# ALLOCHIS_ADAPTER_v1_0.net
KiCad netlist of a schematic drawn in Altium Designer
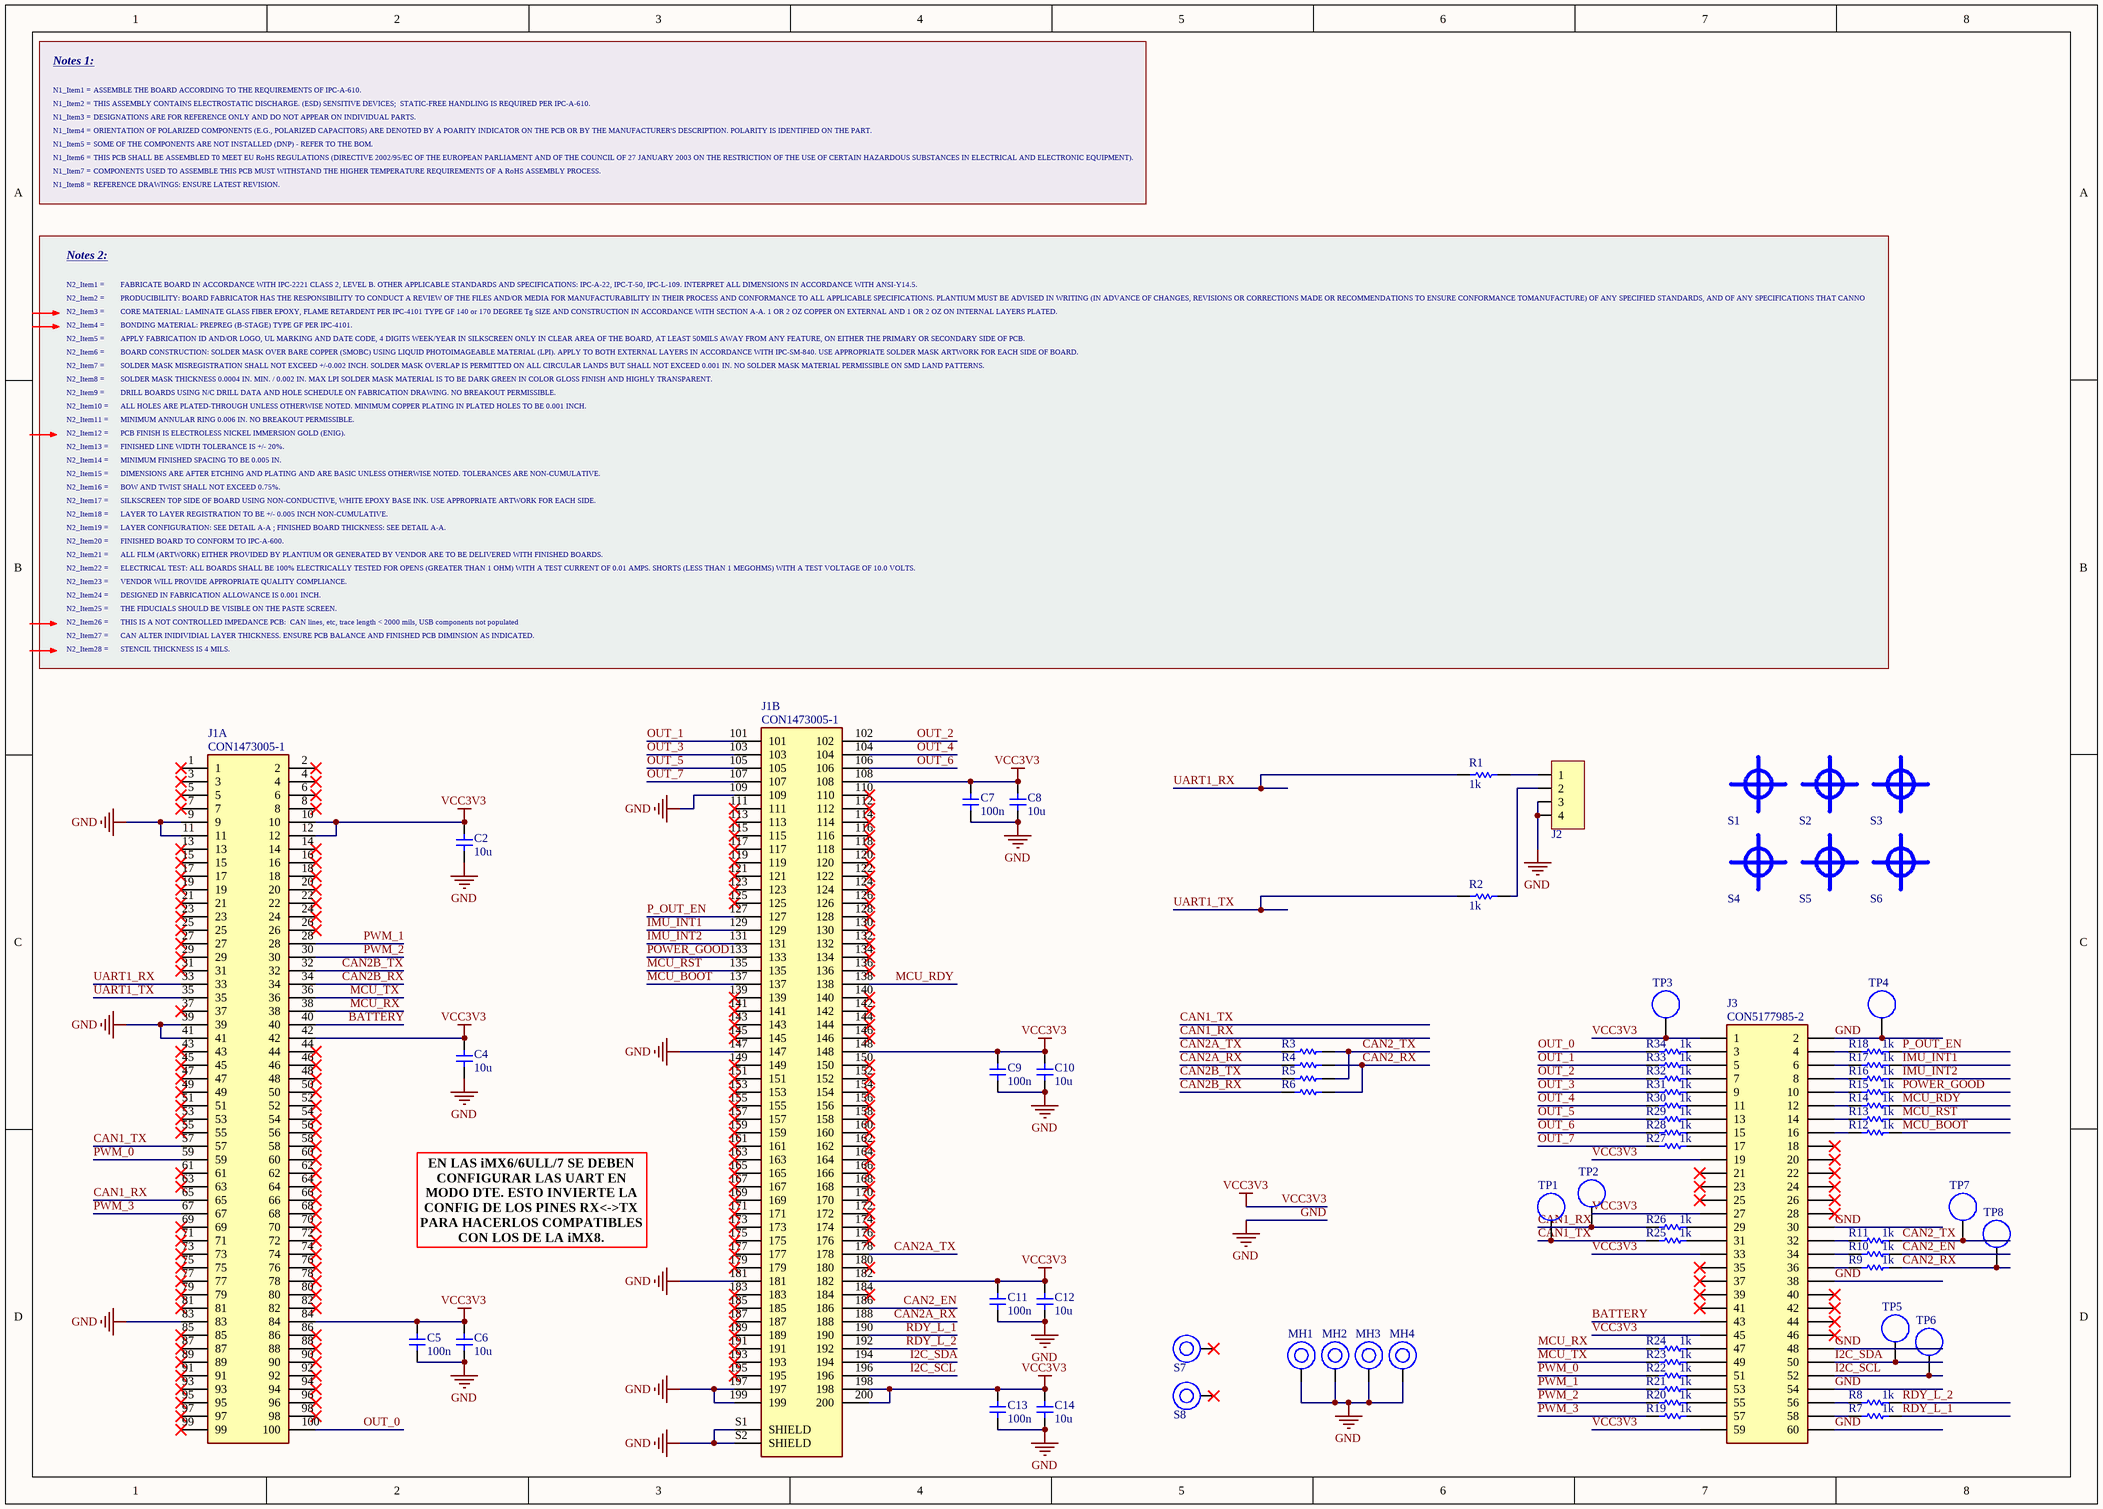
[diagram p0: ALLOCHIS_ADAPTER_v1.0.SchDoc]

(export (version "E")
  (design (tool "Eeschema 10.0.6"))
  (components
    (comp (ref "AssemblyNotes")
      (value "AssemblyNotes")
      (footprint "PlantiumFormat:ASSNOTES")
      (description "Assembly Notes")
      (fields
        (field (name "N1_ITEM8") "REFERENCE DRAWINGS: ENSURE LATEST REVISION.")
        (field (name "N1_ITEM7") "COMPONENTS USED TO ASSEMBLE THIS PCB MUST WITHSTAND THE HIGHER TEMPERATURE REQUIREMENTS OF A RoHS ASSEMBLY PROCESS.")
        (field (name "N1_ITEM6") "THIS PCB SHALL BE ASSEMBLED T0 MEET EU RoHS REGULATIONS (DIRECTIVE 2002/95/EC OF THE EUROPEAN PARLIAMENT AND OF THE COUNCIL OF 27 JANUARY 2003 ON THE RESTRICTION OF THE USE OF CERTAIN HAZARDOUS SUBSTANCES IN ELECTRICAL AND ELECTRONIC EQUIPMENT).")
        (field (name "N1_ITEM5") "SOME OF THE COMPONENTS ARE NOT INSTALLED (DNP) - REFER TO THE BOM.")
        (field (name "N1_ITEM4") "ORIENTATION OF POLARIZED COMPONENTS (E.G., POLARIZED CAPACITORS) ARE DENOTED BY A POARITY INDICATOR ON THE PCB OR BY THE MANUFACTURER'S DESCRIPTION. POLARITY IS IDENTIFIED ON THE PART.")
        (field (name "N1_ITEM3") "DESIGNATIONS ARE FOR REFERENCE ONLY AND DO NOT APPEAR ON INDIVIDUAL PARTS.")
        (field (name "N1_ITEM2") "THIS ASSEMBLY CONTAINS ELECTROSTATIC DISCHARGE. (ESD) SENSITIVE DEVICES;  STATIC-FREE HANDLING IS REQUIRED PER IPC-A-610.")
        (field (name "N1_ITEM1") "ASSEMBLE THE BOARD ACCORDING TO THE REQUIREMENTS OF IPC-A-610.")
      )
      (libsource (lib "PlantiumFormat") (part "AssemblyNotes"))
    )
    (comp (ref "C2")
      (value "10u")
      (footprint "C1206")
      (description "10 µF ±10% 50V Ceramic Capacitor X7R 1206 (3216 Metric)")
      (fields (field (name "MANUFACTURER PART NUMBER") "CL31B106KBHNNNE") (field (name "POWER") "NC"))
      (libsource (lib "PlantiumIntegratedLibrary") (part "CC106HKB1206W"))
    )
    (comp (ref "C4")
      (value "10u")
      (footprint "C1206")
      (description "10 µF ±10% 50V Ceramic Capacitor X7R 1206 (3216 Metric)")
      (fields (field (name "MANUFACTURER PART NUMBER") "CL31B106KBHNNNE") (field (name "POWER") "NC"))
      (libsource (lib "PlantiumIntegratedLibrary") (part "CC106HKB1206W"))
    )
    (comp (ref "C5")
      (value "100n")
      (footprint "C0603")
      (description "100 nF ±10% 50V Ceramic Capacitor X7R 0603 (1608 Metric)")
      (fields (field (name "MANUFACTURER PART NUMBER") "C0603C104K5RACTU") (field (name "POWER") "NC"))
      (libsource (lib "PlantiumIntegratedLibrary") (part "CC104HKB0603W"))
    )
    (comp (ref "C6")
      (value "10u")
      (footprint "C1206")
      (description "10 µF ±10% 50V Ceramic Capacitor X7R 1206 (3216 Metric)")
      (fields (field (name "MANUFACTURER PART NUMBER") "CL31B106KBHNNNE") (field (name "POWER") "NC"))
      (libsource (lib "PlantiumIntegratedLibrary") (part "CC106HKB1206W"))
    )
    (comp (ref "C7")
      (value "100n")
      (footprint "C0603")
      (description "100 nF ±10% 50V Ceramic Capacitor X7R 0603 (1608 Metric)")
      (fields (field (name "MANUFACTURER PART NUMBER") "C0603C104K5RACTU") (field (name "POWER") "NC"))
      (libsource (lib "PlantiumIntegratedLibrary") (part "CC104HKB0603W"))
    )
    (comp (ref "C8")
      (value "10u")
      (footprint "C1206")
      (description "10 µF ±10% 50V Ceramic Capacitor X7R 1206 (3216 Metric)")
      (fields (field (name "MANUFACTURER PART NUMBER") "CL31B106KBHNNNE") (field (name "POWER") "NC"))
      (libsource (lib "PlantiumIntegratedLibrary") (part "CC106HKB1206W"))
    )
    (comp (ref "C9")
      (value "100n")
      (footprint "C0603")
      (description "100 nF ±10% 50V Ceramic Capacitor X7R 0603 (1608 Metric)")
      (fields (field (name "MANUFACTURER PART NUMBER") "C0603C104K5RACTU") (field (name "POWER") "NC"))
      (libsource (lib "PlantiumIntegratedLibrary") (part "CC104HKB0603W"))
    )
    (comp (ref "C10")
      (value "10u")
      (footprint "C1206")
      (description "10 µF ±10% 50V Ceramic Capacitor X7R 1206 (3216 Metric)")
      (fields (field (name "MANUFACTURER PART NUMBER") "CL31B106KBHNNNE") (field (name "POWER") "NC"))
      (libsource (lib "PlantiumIntegratedLibrary") (part "CC106HKB1206W"))
    )
    (comp (ref "C11")
      (value "100n")
      (footprint "C0603")
      (description "100 nF ±10% 50V Ceramic Capacitor X7R 0603 (1608 Metric)")
      (fields (field (name "MANUFACTURER PART NUMBER") "C0603C104K5RACTU") (field (name "POWER") "NC"))
      (libsource (lib "PlantiumIntegratedLibrary") (part "CC104HKB0603W"))
    )
    (comp (ref "C12")
      (value "10u")
      (footprint "C1206")
      (description "10 µF ±10% 50V Ceramic Capacitor X7R 1206 (3216 Metric)")
      (fields (field (name "MANUFACTURER PART NUMBER") "CL31B106KBHNNNE") (field (name "POWER") "NC"))
      (libsource (lib "PlantiumIntegratedLibrary") (part "CC106HKB1206W"))
    )
    (comp (ref "C13")
      (value "100n")
      (footprint "C0603")
      (description "100 nF ±10% 50V Ceramic Capacitor X7R 0603 (1608 Metric)")
      (fields (field (name "MANUFACTURER PART NUMBER") "C0603C104K5RACTU") (field (name "POWER") "NC"))
      (libsource (lib "PlantiumIntegratedLibrary") (part "CC104HKB0603W"))
    )
    (comp (ref "C14")
      (value "10u")
      (footprint "C1206")
      (description "10 µF ±10% 50V Ceramic Capacitor X7R 1206 (3216 Metric)")
      (fields (field (name "MANUFACTURER PART NUMBER") "CL31B106KBHNNNE") (field (name "POWER") "NC"))
      (libsource (lib "PlantiumIntegratedLibrary") (part "CC106HKB1206W"))
    )
    (comp (ref "Fabrication Notes")
      (value "FabricationNotes")
      (footprint "PlantiumFormat:FABNOTES")
      (description "Fabrication Notes")
      (fields
        (field (name "N2_ITEM28") "STENCIL THICKNESS IS 4 MILS.")
        (field (name "N2_ITEM27") "CAN ALTER INIDIVIDIAL LAYER THICKNESS. ENSURE PCB BALANCE AND FINISHED PCB DIMINSION AS INDICATED.")
        (field (name "N2_ITEM26") "THIS IS A NOT CONTROLLED IMPEDANCE PCB:  CAN lines, etc, trace length < 2000 mils, USB components not populated")
        (field (name "N2_ITEM25") "THE FIDUCIALS SHOULD BE VISIBLE ON THE PASTE SCREEN.")
        (field (name "N2_ITEM24") "DESIGNED IN FABRICATION ALLOWANCE IS 0.001 INCH.")
        (field (name "N2_ITEM23") "VENDOR WILL PROVIDE APPROPRIATE QUALITY COMPLIANCE.")
        (field (name "N2_ITEM22") "ELECTRICAL TEST: ALL BOARDS SHALL BE 100% ELECTRICALLY TESTED FOR OPENS (GREATER THAN 1 OHM) WITH A TEST CURRENT OF 0.01 AMPS. SHORTS (LESS THAN 1 MEGOHMS) WITH A TEST VOLTAGE OF 10.0 VOLTS.")
        (field (name "N2_ITEM21") "ALL FILM (ARTWORK) EITHER PROVIDED BY PLANTIUM OR GENERATED BY VENDOR ARE TO BE DELIVERED WITH FINISHED BOARDS.")
        (field (name "N2_ITEM20") "FINISHED BOARD TO CONFORM TO IPC-A-600.")
        (field (name "N2_ITEM19") "LAYER CONFIGURATION: SEE DETAIL A-A ; FINISHED BOARD THICKNESS: SEE DETAIL A-A.")
        (field (name "N2_ITEM18") "LAYER TO LAYER REGISTRATION TO BE +/- 0.005 INCH NON-CUMULATIVE.")
        (field (name "N2_ITEM17") "SILKSCREEN TOP SIDE OF BOARD USING NON-CONDUCTIVE, WHITE EPOXY BASE INK. USE APPROPRIATE ARTWORK FOR EACH SIDE.")
        (field (name "N2_ITEM16") "BOW AND TWIST SHALL NOT EXCEED 0.75%.")
        (field (name "N2_ITEM15") "DIMENSIONS ARE AFTER ETCHING AND PLATING AND ARE BASIC UNLESS OTHERWISE NOTED. TOLERANCES ARE NON-CUMULATIVE.")
        (field (name "N2_ITEM14") "MINIMUM FINISHED SPACING TO BE 0.005 IN.")
        (field (name "N2_ITEM13") "FINISHED LINE WIDTH TOLERANCE IS +/- 20%.")
        (field (name "N2_ITEM12") "PCB FINISH IS ELECTROLESS NICKEL IMMERSION GOLD (ENIG).")
        (field (name "N2_ITEM11") "MINIMUM ANNULAR RING 0.006 IN. NO BREAKOUT PERMISSIBLE.")
        (field (name "N2_ITEM10") "ALL HOLES ARE PLATED-THROUGH UNLESS OTHERWISE NOTED. MINIMUM COPPER PLATING IN PLATED HOLES TO BE 0.001 INCH.")
        (field (name "N2_ITEM9") "DRILL BOARDS USING N/C DRILL DATA AND HOLE SCHEDULE ON FABRICATION DRAWING. NO BREAKOUT PERMISSIBLE.")
        (field (name "N2_ITEM8") "SOLDER MASK THICKNESS 0.0004 IN. MIN. / 0.002 IN. MAX LPI SOLDER MASK MATERIAL IS TO BE DARK GREEN IN COLOR GLOSS FINISH AND HIGHLY TRANSPARENT.")
        (field (name "N2_ITEM7") "SOLDER MASK MISREGISTRATION SHALL NOT EXCEED +/-0.002 INCH. SOLDER MASK OVERLAP IS PERMITTED ON ALL CIRCULAR LANDS BUT SHALL NOT EXCEED 0.001 IN. NO SOLDER MASK MATERIAL PERMISSIBLE ON SMD LAND PATTERNS.")
        (field (name "N2_ITEM6") "BOARD CONSTRUCTION: SOLDER MASK OVER BARE COPPER (SMOBC) USING LIQUID PHOTOIMAGEABLE MATERIAL (LPI). APPLY TO BOTH EXTERNAL LAYERS IN ACCORDANCE WITH IPC-SM-840. USE APPROPRIATE SOLDER MASK ARTWORK FOR EACH SIDE OF BOARD.")
        (field (name "N2_ITEM5") "APPLY FABRICATION ID AND/OR LOGO, UL MARKING AND DATE CODE, 4 DIGITS WEEK/YEAR IN SILKSCREEN ONLY IN CLEAR AREA OF THE BOARD, AT LEAST 50MILS AWAY FROM ANY FEATURE, ON EITHER THE PRIMARY OR SECONDARY SIDE OF PCB.")
        (field (name "N2_ITEM4") "BONDING MATERIAL: PREPREG (B-STAGE) TYPE GF PER IPC-4101.")
        (field (name "N2_ITEM3") "CORE MATERIAL: LAMINATE GLASS FIBER EPOXY, FLAME RETARDENT PER IPC-4101 TYPE GF 140 or 170 DEGREE Tg SIZE AND CONSTRUCTION IN ACCORDANCE WITH SECTION A-A. 1 OR 2 OZ COPPER ON EXTERNAL AND 1 OR 2 OZ ON INTERNAL LAYERS PLATED.")
        (field (name "N2_ITEM2") "PRODUCIBILITY: BOARD FABRICATOR HAS THE RESPONSIBILITY TO CONDUCT A REVIEW OF THE FILES AND/OR MEDIA FOR MANUFACTURABILITY IN THEIR PROCESS AND CONFORMANCE TO ALL APPLICABLE SPECIFICATIONS. PLANTIUM MUST BE ADVISED IN WRITING (IN ADVANCE OF CHANGES, REVISIONS OR CORRECTIONS MADE OR RECOMMENDATIONS TO ENSURE CONFORMANCE TOMANUFACTURE) OF ANY SPECIFIED STANDARDS, AND OF ANY SPECIFICATIONS THAT CANNOT BE MET.")
        (field (name "N2_ITEM1") "FABRICATE BOARD IN ACCORDANCE WITH IPC-2221 CLASS 2, LEVEL B. OTHER APPLICABLE STANDARDS AND SPECIFICATIONS: IPC-A-22, IPC-T-50, IPC-L-109. INTERPRET ALL DIMENSIONS IN ACCORDANCE WITH ANSI-Y14.5.")
      )
      (libsource (lib "PlantiumFormat") (part "FabricationNotes"))
    )
    (comp (ref "J1")
      (value "CON1473005-1")
      (footprint "TE_1473005-1 + SOM Toradex iMX")
      (description "200 Position Dual Row Right Angle Double Data Rate SO DIMM Memory Card Socket")
      (fields
        (field (name "MANUFACTURER PART NUMBER") "1473005-1")
        (field (name "MANUFACTURER") "TE Connectivity")
      )
      (libsource (lib "PlantiumIntegratedLibrary") (part "CON1473005-1"))
    )
    (comp (ref "J2")
      (value "CON-HEADER4")
      (footprint "HEADER4")
      (description "Header, 4-Pin")
      (libsource (lib "PlantiumIntegratedLibrary") (part "CON-HEADER4"))
    )
    (comp (ref "J3")
      (value "CON5177985-2")
      (footprint "TE_5177985-2")
      (description "60 Position Connector Receptacle, SMD, pitch 0.8mm")
      (fields
        (field (name "MANUFACTURER PART NUMBER") "5177985-2")
        (field (name "MANUFACTURER") "TE Connectivity AMP Connectors")
      )
      (libsource (lib "PlantiumIntegratedLibrary") (part "CON5177985-2"))
    )
    (comp (ref "MH1")
      (value "Mounting_Hole")
      (footprint "mounting_hole")
      (description "Mounting Hole")
      (fields (field (name "MANUFACTURER PART NUMBER") "NC"))
      (libsource (lib "PlantiumIntegratedLibrary") (part "Mounting_Hole"))
    )
    (comp (ref "MH2")
      (value "Mounting_Hole")
      (footprint "mounting_hole")
      (description "Mounting Hole")
      (fields (field (name "MANUFACTURER PART NUMBER") "NC"))
      (libsource (lib "PlantiumIntegratedLibrary") (part "Mounting_Hole"))
    )
    (comp (ref "MH3")
      (value "Mounting_Hole")
      (footprint "mounting_hole")
      (description "Mounting Hole")
      (fields (field (name "MANUFACTURER PART NUMBER") "NC"))
      (libsource (lib "PlantiumIntegratedLibrary") (part "Mounting_Hole"))
    )
    (comp (ref "MH4")
      (value "Mounting_Hole")
      (footprint "mounting_hole")
      (description "Mounting Hole")
      (fields (field (name "MANUFACTURER PART NUMBER") "NC"))
      (libsource (lib "PlantiumIntegratedLibrary") (part "Mounting_Hole"))
    )
    (comp (ref "R1")
      (value "1k")
      (footprint "R0603")
      (description "1 kOhms ±1% 0.1W, 1/10W Chip Resistor 0603 (1608 Metric) Automotive AEC-Q200 Thick Film")
      (fields (field (name "MANUFACTURER PART NUMBER") "ERJ-3EKF1001V") (field (name "POWER") "1/10W"))
      (libsource (lib "PlantiumIntegratedLibrary") (part "R1001RLF0603"))
    )
    (comp (ref "R2")
      (value "1k")
      (footprint "R0603")
      (description "1 kOhms ±1% 0.1W, 1/10W Chip Resistor 0603 (1608 Metric) Automotive AEC-Q200 Thick Film")
      (fields (field (name "MANUFACTURER PART NUMBER") "ERJ-3EKF1001V") (field (name "POWER") "1/10W"))
      (libsource (lib "PlantiumIntegratedLibrary") (part "R1001RLF0603"))
    )
    (comp (ref "R3")
      (value "R0000RLX0603")
      (footprint "R0603")
      (description "0 Ohms Jumper 0.1W, 1/10W Chip Resistor 0603 (1608 Metric) Automotive AEC-Q200 Thick Film")
      (fields (field (name "MANUFACTURER PART NUMBER") "ERJ-3GEY0R00V") (field (name "POWER") "1/10W"))
      (libsource (lib "PlantiumIntegratedLibrary") (part "R0000RLX0603"))
    )
    (comp (ref "R4")
      (value "R0000RLX0603")
      (footprint "R0603")
      (description "0 Ohms Jumper 0.1W, 1/10W Chip Resistor 0603 (1608 Metric) Automotive AEC-Q200 Thick Film")
      (fields (field (name "MANUFACTURER PART NUMBER") "ERJ-3GEY0R00V") (field (name "POWER") "1/10W"))
      (libsource (lib "PlantiumIntegratedLibrary") (part "R0000RLX0603"))
    )
    (comp (ref "R5")
      (value "R0000RLX0603")
      (footprint "R0603")
      (description "0 Ohms Jumper 0.1W, 1/10W Chip Resistor 0603 (1608 Metric) Automotive AEC-Q200 Thick Film")
      (fields (field (name "MANUFACTURER PART NUMBER") "ERJ-3GEY0R00V") (field (name "POWER") "1/10W"))
      (libsource (lib "PlantiumIntegratedLibrary") (part "R0000RLX0603"))
    )
    (comp (ref "R6")
      (value "R0000RLX0603")
      (footprint "R0603")
      (description "0 Ohms Jumper 0.1W, 1/10W Chip Resistor 0603 (1608 Metric) Automotive AEC-Q200 Thick Film")
      (fields (field (name "MANUFACTURER PART NUMBER") "ERJ-3GEY0R00V") (field (name "POWER") "1/10W"))
      (libsource (lib "PlantiumIntegratedLibrary") (part "R0000RLX0603"))
    )
    (comp (ref "R7")
      (value "1k")
      (footprint "R0603")
      (description "1 kOhms ±1% 0.1W, 1/10W Chip Resistor 0603 (1608 Metric) Automotive AEC-Q200 Thick Film")
      (fields (field (name "MANUFACTURER PART NUMBER") "ERJ-3EKF1001V") (field (name "POWER") "1/10W"))
      (libsource (lib "PlantiumIntegratedLibrary") (part "R1001RLF0603"))
    )
    (comp (ref "R8")
      (value "1k")
      (footprint "R0603")
      (description "1 kOhms ±1% 0.1W, 1/10W Chip Resistor 0603 (1608 Metric) Automotive AEC-Q200 Thick Film")
      (fields (field (name "MANUFACTURER PART NUMBER") "ERJ-3EKF1001V") (field (name "POWER") "1/10W"))
      (libsource (lib "PlantiumIntegratedLibrary") (part "R1001RLF0603"))
    )
    (comp (ref "R9")
      (value "1k")
      (footprint "R0603")
      (description "1 kOhms ±1% 0.1W, 1/10W Chip Resistor 0603 (1608 Metric) Automotive AEC-Q200 Thick Film")
      (fields (field (name "MANUFACTURER PART NUMBER") "ERJ-3EKF1001V") (field (name "POWER") "1/10W"))
      (libsource (lib "PlantiumIntegratedLibrary") (part "R1001RLF0603"))
    )
    (comp (ref "R10")
      (value "1k")
      (footprint "R0603")
      (description "1 kOhms ±1% 0.1W, 1/10W Chip Resistor 0603 (1608 Metric) Automotive AEC-Q200 Thick Film")
      (fields (field (name "MANUFACTURER PART NUMBER") "ERJ-3EKF1001V") (field (name "POWER") "1/10W"))
      (libsource (lib "PlantiumIntegratedLibrary") (part "R1001RLF0603"))
    )
    (comp (ref "R11")
      (value "1k")
      (footprint "R0603")
      (description "1 kOhms ±1% 0.1W, 1/10W Chip Resistor 0603 (1608 Metric) Automotive AEC-Q200 Thick Film")
      (fields (field (name "MANUFACTURER PART NUMBER") "ERJ-3EKF1001V") (field (name "POWER") "1/10W"))
      (libsource (lib "PlantiumIntegratedLibrary") (part "R1001RLF0603"))
    )
    (comp (ref "R12")
      (value "1k")
      (footprint "R0603")
      (description "1 kOhms ±1% 0.1W, 1/10W Chip Resistor 0603 (1608 Metric) Automotive AEC-Q200 Thick Film")
      (fields (field (name "MANUFACTURER PART NUMBER") "ERJ-3EKF1001V") (field (name "POWER") "1/10W"))
      (libsource (lib "PlantiumIntegratedLibrary") (part "R1001RLF0603"))
    )
    (comp (ref "R13")
      (value "1k")
      (footprint "R0603")
      (description "1 kOhms ±1% 0.1W, 1/10W Chip Resistor 0603 (1608 Metric) Automotive AEC-Q200 Thick Film")
      (fields (field (name "MANUFACTURER PART NUMBER") "ERJ-3EKF1001V") (field (name "POWER") "1/10W"))
      (libsource (lib "PlantiumIntegratedLibrary") (part "R1001RLF0603"))
    )
    (comp (ref "R14")
      (value "1k")
      (footprint "R0603")
      (description "1 kOhms ±1% 0.1W, 1/10W Chip Resistor 0603 (1608 Metric) Automotive AEC-Q200 Thick Film")
      (fields (field (name "MANUFACTURER PART NUMBER") "ERJ-3EKF1001V") (field (name "POWER") "1/10W"))
      (libsource (lib "PlantiumIntegratedLibrary") (part "R1001RLF0603"))
    )
    (comp (ref "R15")
      (value "1k")
      (footprint "R0603")
      (description "1 kOhms ±1% 0.1W, 1/10W Chip Resistor 0603 (1608 Metric) Automotive AEC-Q200 Thick Film")
      (fields (field (name "MANUFACTURER PART NUMBER") "ERJ-3EKF1001V") (field (name "POWER") "1/10W"))
      (libsource (lib "PlantiumIntegratedLibrary") (part "R1001RLF0603"))
    )
    (comp (ref "R16")
      (value "1k")
      (footprint "R0603")
      (description "1 kOhms ±1% 0.1W, 1/10W Chip Resistor 0603 (1608 Metric) Automotive AEC-Q200 Thick Film")
      (fields (field (name "MANUFACTURER PART NUMBER") "ERJ-3EKF1001V") (field (name "POWER") "1/10W"))
      (libsource (lib "PlantiumIntegratedLibrary") (part "R1001RLF0603"))
    )
    (comp (ref "R17")
      (value "1k")
      (footprint "R0603")
      (description "1 kOhms ±1% 0.1W, 1/10W Chip Resistor 0603 (1608 Metric) Automotive AEC-Q200 Thick Film")
      (fields (field (name "MANUFACTURER PART NUMBER") "ERJ-3EKF1001V") (field (name "POWER") "1/10W"))
      (libsource (lib "PlantiumIntegratedLibrary") (part "R1001RLF0603"))
    )
    (comp (ref "R18")
      (value "1k")
      (footprint "R0603")
      (description "1 kOhms ±1% 0.1W, 1/10W Chip Resistor 0603 (1608 Metric) Automotive AEC-Q200 Thick Film")
      (fields (field (name "MANUFACTURER PART NUMBER") "ERJ-3EKF1001V") (field (name "POWER") "1/10W"))
      (libsource (lib "PlantiumIntegratedLibrary") (part "R1001RLF0603"))
    )
    (comp (ref "R19")
      (value "1k")
      (footprint "R0603")
      (description "1 kOhms ±1% 0.1W, 1/10W Chip Resistor 0603 (1608 Metric) Automotive AEC-Q200 Thick Film")
      (fields (field (name "MANUFACTURER PART NUMBER") "ERJ-3EKF1001V") (field (name "POWER") "1/10W"))
      (libsource (lib "PlantiumIntegratedLibrary") (part "R1001RLF0603"))
    )
    (comp (ref "R20")
      (value "1k")
      (footprint "R0603")
      (description "1 kOhms ±1% 0.1W, 1/10W Chip Resistor 0603 (1608 Metric) Automotive AEC-Q200 Thick Film")
      (fields (field (name "MANUFACTURER PART NUMBER") "ERJ-3EKF1001V") (field (name "POWER") "1/10W"))
      (libsource (lib "PlantiumIntegratedLibrary") (part "R1001RLF0603"))
    )
    (comp (ref "R21")
      (value "1k")
      (footprint "R0603")
      (description "1 kOhms ±1% 0.1W, 1/10W Chip Resistor 0603 (1608 Metric) Automotive AEC-Q200 Thick Film")
      (fields (field (name "MANUFACTURER PART NUMBER") "ERJ-3EKF1001V") (field (name "POWER") "1/10W"))
      (libsource (lib "PlantiumIntegratedLibrary") (part "R1001RLF0603"))
    )
    (comp (ref "R22")
      (value "1k")
      (footprint "R0603")
      (description "1 kOhms ±1% 0.1W, 1/10W Chip Resistor 0603 (1608 Metric) Automotive AEC-Q200 Thick Film")
      (fields (field (name "MANUFACTURER PART NUMBER") "ERJ-3EKF1001V") (field (name "POWER") "1/10W"))
      (libsource (lib "PlantiumIntegratedLibrary") (part "R1001RLF0603"))
    )
    (comp (ref "R23")
      (value "1k")
      (footprint "R0603")
      (description "1 kOhms ±1% 0.1W, 1/10W Chip Resistor 0603 (1608 Metric) Automotive AEC-Q200 Thick Film")
      (fields (field (name "MANUFACTURER PART NUMBER") "ERJ-3EKF1001V") (field (name "POWER") "1/10W"))
      (libsource (lib "PlantiumIntegratedLibrary") (part "R1001RLF0603"))
    )
    (comp (ref "R24")
      (value "1k")
      (footprint "R0603")
      (description "1 kOhms ±1% 0.1W, 1/10W Chip Resistor 0603 (1608 Metric) Automotive AEC-Q200 Thick Film")
      (fields (field (name "MANUFACTURER PART NUMBER") "ERJ-3EKF1001V") (field (name "POWER") "1/10W"))
      (libsource (lib "PlantiumIntegratedLibrary") (part "R1001RLF0603"))
    )
    (comp (ref "R25")
      (value "1k")
      (footprint "R0603")
      (description "1 kOhms ±1% 0.1W, 1/10W Chip Resistor 0603 (1608 Metric) Automotive AEC-Q200 Thick Film")
      (fields (field (name "MANUFACTURER PART NUMBER") "ERJ-3EKF1001V") (field (name "POWER") "1/10W"))
      (libsource (lib "PlantiumIntegratedLibrary") (part "R1001RLF0603"))
    )
    (comp (ref "R26")
      (value "1k")
      (footprint "R0603")
      (description "1 kOhms ±1% 0.1W, 1/10W Chip Resistor 0603 (1608 Metric) Automotive AEC-Q200 Thick Film")
      (fields (field (name "MANUFACTURER PART NUMBER") "ERJ-3EKF1001V") (field (name "POWER") "1/10W"))
      (libsource (lib "PlantiumIntegratedLibrary") (part "R1001RLF0603"))
    )
    (comp (ref "R27")
      (value "1k")
      (footprint "R0603")
      (description "1 kOhms ±1% 0.1W, 1/10W Chip Resistor 0603 (1608 Metric) Automotive AEC-Q200 Thick Film")
      (fields (field (name "MANUFACTURER PART NUMBER") "ERJ-3EKF1001V") (field (name "POWER") "1/10W"))
      (libsource (lib "PlantiumIntegratedLibrary") (part "R1001RLF0603"))
    )
    (comp (ref "R28")
      (value "1k")
      (footprint "R0603")
      (description "1 kOhms ±1% 0.1W, 1/10W Chip Resistor 0603 (1608 Metric) Automotive AEC-Q200 Thick Film")
      (fields (field (name "MANUFACTURER PART NUMBER") "ERJ-3EKF1001V") (field (name "POWER") "1/10W"))
      (libsource (lib "PlantiumIntegratedLibrary") (part "R1001RLF0603"))
    )
    (comp (ref "R29")
      (value "1k")
      (footprint "R0603")
      (description "1 kOhms ±1% 0.1W, 1/10W Chip Resistor 0603 (1608 Metric) Automotive AEC-Q200 Thick Film")
      (fields (field (name "MANUFACTURER PART NUMBER") "ERJ-3EKF1001V") (field (name "POWER") "1/10W"))
      (libsource (lib "PlantiumIntegratedLibrary") (part "R1001RLF0603"))
    )
    (comp (ref "R30")
      (value "1k")
      (footprint "R0603")
      (description "1 kOhms ±1% 0.1W, 1/10W Chip Resistor 0603 (1608 Metric) Automotive AEC-Q200 Thick Film")
      (fields (field (name "MANUFACTURER PART NUMBER") "ERJ-3EKF1001V") (field (name "POWER") "1/10W"))
      (libsource (lib "PlantiumIntegratedLibrary") (part "R1001RLF0603"))
    )
    (comp (ref "R31")
      (value "1k")
      (footprint "R0603")
      (description "1 kOhms ±1% 0.1W, 1/10W Chip Resistor 0603 (1608 Metric) Automotive AEC-Q200 Thick Film")
      (fields (field (name "MANUFACTURER PART NUMBER") "ERJ-3EKF1001V") (field (name "POWER") "1/10W"))
      (libsource (lib "PlantiumIntegratedLibrary") (part "R1001RLF0603"))
    )
    (comp (ref "R32")
      (value "1k")
      (footprint "R0603")
      (description "1 kOhms ±1% 0.1W, 1/10W Chip Resistor 0603 (1608 Metric) Automotive AEC-Q200 Thick Film")
      (fields (field (name "MANUFACTURER PART NUMBER") "ERJ-3EKF1001V") (field (name "POWER") "1/10W"))
      (libsource (lib "PlantiumIntegratedLibrary") (part "R1001RLF0603"))
    )
    (comp (ref "R33")
      (value "1k")
      (footprint "R0603")
      (description "1 kOhms ±1% 0.1W, 1/10W Chip Resistor 0603 (1608 Metric) Automotive AEC-Q200 Thick Film")
      (fields (field (name "MANUFACTURER PART NUMBER") "ERJ-3EKF1001V") (field (name "POWER") "1/10W"))
      (libsource (lib "PlantiumIntegratedLibrary") (part "R1001RLF0603"))
    )
    (comp (ref "R34")
      (value "1k")
      (footprint "R0603")
      (description "1 kOhms ±1% 0.1W, 1/10W Chip Resistor 0603 (1608 Metric) Automotive AEC-Q200 Thick Film")
      (fields (field (name "MANUFACTURER PART NUMBER") "ERJ-3EKF1001V") (field (name "POWER") "1/10W"))
      (libsource (lib "PlantiumIntegratedLibrary") (part "R1001RLF0603"))
    )
    (comp (ref "S1")
      (value "Fiducial")
      (footprint "FIDROUND1X2")
      (description "Fiducial Mark")
      (fields (field (name "TOLERANCE") "NC"))
      (libsource (lib "PlantiumIntegratedLibrary") (part "Fiducial"))
    )
    (comp (ref "S2")
      (value "Fiducial")
      (footprint "FIDROUND1X2")
      (description "Fiducial Mark")
      (fields (field (name "TOLERANCE") "NC"))
      (libsource (lib "PlantiumIntegratedLibrary") (part "Fiducial"))
    )
    (comp (ref "S3")
      (value "Fiducial")
      (footprint "FIDROUND1X2")
      (description "Fiducial Mark")
      (fields (field (name "TOLERANCE") "NC"))
      (libsource (lib "PlantiumIntegratedLibrary") (part "Fiducial"))
    )
    (comp (ref "S4")
      (value "Fiducial")
      (footprint "FIDROUND1X2")
      (description "Fiducial Mark")
      (fields (field (name "TOLERANCE") "NC"))
      (libsource (lib "PlantiumIntegratedLibrary") (part "Fiducial"))
    )
    (comp (ref "S5")
      (value "Fiducial")
      (footprint "FIDROUND1X2")
      (description "Fiducial Mark")
      (fields (field (name "TOLERANCE") "NC"))
      (libsource (lib "PlantiumIntegratedLibrary") (part "Fiducial"))
    )
    (comp (ref "S6")
      (value "Fiducial")
      (footprint "FIDROUND1X2")
      (description "Fiducial Mark")
      (fields (field (name "TOLERANCE") "NC"))
      (libsource (lib "PlantiumIntegratedLibrary") (part "Fiducial"))
    )
    (comp (ref "S7")
      (value "ACC74030243R")
      (footprint "9774030243")
      (description "Steel Spacer. Round Standoff Threaded M2x0.4 Steel 0.118\" (3.00mm)")
      (fields
        (field (name "MANUFACTURER PART NUMBER") "9774030243R")
        (field (name "MANUFACTURER") "Würth Elektronik")
      )
      (libsource (lib "PlantiumIntegratedLibrary") (part "ACC74030243R"))
    )
    (comp (ref "S8")
      (value "ACC74030243R")
      (footprint "9774030243")
      (description "Steel Spacer. Round Standoff Threaded M2x0.4 Steel 0.118\" (3.00mm)")
      (fields
        (field (name "MANUFACTURER PART NUMBER") "9774030243R")
        (field (name "MANUFACTURER") "Würth Elektronik")
      )
      (libsource (lib "PlantiumIntegratedLibrary") (part "ACC74030243R"))
    )
    (comp (ref "TP1")
      (value "Test_Point")
      (footprint "Test_point")
      (description "Test point")
      (fields (field (name "MANUFACTURER PART NUMBER") "NC"))
      (libsource (lib "PlantiumIntegratedLibrary") (part "Test_Point"))
    )
    (comp (ref "TP2")
      (value "Test_Point")
      (footprint "Test_point")
      (description "Test point")
      (fields (field (name "MANUFACTURER PART NUMBER") "NC"))
      (libsource (lib "PlantiumIntegratedLibrary") (part "Test_Point"))
    )
    (comp (ref "TP3")
      (value "Test_Point")
      (footprint "Test_point")
      (description "Test point")
      (fields (field (name "MANUFACTURER PART NUMBER") "NC"))
      (libsource (lib "PlantiumIntegratedLibrary") (part "Test_Point"))
    )
    (comp (ref "TP4")
      (value "Test_Point")
      (footprint "Test_point")
      (description "Test point")
      (fields (field (name "MANUFACTURER PART NUMBER") "NC"))
      (libsource (lib "PlantiumIntegratedLibrary") (part "Test_Point"))
    )
    (comp (ref "TP5")
      (value "Test_Point")
      (footprint "Test_point")
      (description "Test point")
      (fields (field (name "MANUFACTURER PART NUMBER") "NC"))
      (libsource (lib "PlantiumIntegratedLibrary") (part "Test_Point"))
    )
    (comp (ref "TP6")
      (value "Test_Point")
      (footprint "Test_point")
      (description "Test point")
      (fields (field (name "MANUFACTURER PART NUMBER") "NC"))
      (libsource (lib "PlantiumIntegratedLibrary") (part "Test_Point"))
    )
    (comp (ref "TP7")
      (value "Test_Point")
      (footprint "Test_point")
      (description "Test point")
      (fields (field (name "MANUFACTURER PART NUMBER") "NC"))
      (libsource (lib "PlantiumIntegratedLibrary") (part "Test_Point"))
    )
    (comp (ref "TP8")
      (value "Test_Point")
      (footprint "Test_point")
      (description "Test point")
      (fields (field (name "MANUFACTURER PART NUMBER") "NC"))
      (libsource (lib "PlantiumIntegratedLibrary") (part "Test_Point"))
    )
  )
  (nets
    (net (code "1") (name "/BATTERY") (class "Default")
      (node (ref "J1") (pin "40") (pinfunction "40_40") (pintype "passive"))
      (node (ref "J3") (pin "43") (pinfunction "43_43") (pintype "passive"))
    )
    (net (code "2") (name "/CAN1_RX") (class "Default")
      (node (ref "J1") (pin "65") (pinfunction "65_65") (pintype "passive"))
      (node (ref "R26") (pin "1") (pinfunction "1_1") (pintype "passive"))
      (node (ref "TP2") (pin "1") (pinfunction "1_1") (pintype "passive"))
    )
    (net (code "3") (name "/CAN1_TX") (class "Default")
      (node (ref "J1") (pin "57") (pinfunction "57_57") (pintype "passive"))
      (node (ref "R25") (pin "1") (pinfunction "1_1") (pintype "passive"))
      (node (ref "TP1") (pin "1") (pinfunction "1_1") (pintype "passive"))
    )
    (net (code "4") (name "/CAN2A_RX") (class "Default")
      (node (ref "J1") (pin "188") (pinfunction "188_188") (pintype "passive"))
      (node (ref "R4") (pin "1") (pinfunction "1_1") (pintype "passive"))
    )
    (net (code "5") (name "/CAN2A_TX") (class "Default")
      (node (ref "J1") (pin "178") (pinfunction "178_178") (pintype "passive"))
      (node (ref "R3") (pin "1") (pinfunction "1_1") (pintype "passive"))
    )
    (net (code "6") (name "/CAN2B_RX") (class "Default")
      (node (ref "J1") (pin "34") (pinfunction "34_34") (pintype "passive"))
      (node (ref "R6") (pin "1") (pinfunction "1_1") (pintype "passive"))
    )
    (net (code "7") (name "/CAN2B_TX") (class "Default")
      (node (ref "J1") (pin "32") (pinfunction "32_32") (pintype "passive"))
      (node (ref "R5") (pin "1") (pinfunction "1_1") (pintype "passive"))
    )
    (net (code "8") (name "/CAN2_EN") (class "Default")
      (node (ref "J1") (pin "186") (pinfunction "186_186") (pintype "passive"))
      (node (ref "R10") (pin "2") (pinfunction "2_2") (pintype "passive"))
    )
    (net (code "9") (name "/CAN2_RX") (class "Default")
      (node (ref "R4") (pin "2") (pinfunction "2_2") (pintype "passive"))
      (node (ref "R6") (pin "2") (pinfunction "2_2") (pintype "passive"))
      (node (ref "R9") (pin "2") (pinfunction "2_2") (pintype "passive"))
      (node (ref "TP8") (pin "1") (pinfunction "1_1") (pintype "passive"))
    )
    (net (code "10") (name "/CAN2_TX") (class "Default")
      (node (ref "R11") (pin "2") (pinfunction "2_2") (pintype "passive"))
      (node (ref "R3") (pin "2") (pinfunction "2_2") (pintype "passive"))
      (node (ref "R5") (pin "2") (pinfunction "2_2") (pintype "passive"))
      (node (ref "TP7") (pin "1") (pinfunction "1_1") (pintype "passive"))
    )
    (net (code "11") (name "/I2C_SCL") (class "Default")
      (node (ref "J1") (pin "196") (pinfunction "196_196") (pintype "passive"))
      (node (ref "J3") (pin "52") (pinfunction "52_52") (pintype "passive"))
      (node (ref "TP6") (pin "1") (pinfunction "1_1") (pintype "passive"))
    )
    (net (code "12") (name "/I2C_SDA") (class "Default")
      (node (ref "J1") (pin "194") (pinfunction "194_194") (pintype "passive"))
      (node (ref "J3") (pin "50") (pinfunction "50_50") (pintype "passive"))
      (node (ref "TP5") (pin "1") (pinfunction "1_1") (pintype "passive"))
    )
    (net (code "13") (name "/IMU_INT1") (class "Default")
      (node (ref "J1") (pin "129") (pinfunction "129_129") (pintype "passive"))
      (node (ref "R17") (pin "2") (pinfunction "2_2") (pintype "passive"))
    )
    (net (code "14") (name "/IMU_INT2") (class "Default")
      (node (ref "J1") (pin "131") (pinfunction "131_131") (pintype "passive"))
      (node (ref "R16") (pin "2") (pinfunction "2_2") (pintype "passive"))
    )
    (net (code "15") (name "/MCU_BOOT") (class "Default")
      (node (ref "J1") (pin "137") (pinfunction "137_137") (pintype "passive"))
      (node (ref "R12") (pin "2") (pinfunction "2_2") (pintype "passive"))
    )
    (net (code "16") (name "/MCU_RDY") (class "Default")
      (node (ref "J1") (pin "138") (pinfunction "138_138") (pintype "passive"))
      (node (ref "R14") (pin "2") (pinfunction "2_2") (pintype "passive"))
    )
    (net (code "17") (name "/MCU_RST") (class "Default")
      (node (ref "J1") (pin "135") (pinfunction "135_135") (pintype "passive"))
      (node (ref "R13") (pin "2") (pinfunction "2_2") (pintype "passive"))
    )
    (net (code "18") (name "/MCU_RX") (class "Default")
      (node (ref "J1") (pin "38") (pinfunction "38_38") (pintype "passive"))
      (node (ref "R24") (pin "1") (pinfunction "1_1") (pintype "passive"))
    )
    (net (code "19") (name "/MCU_TX") (class "Default")
      (node (ref "J1") (pin "36") (pinfunction "36_36") (pintype "passive"))
      (node (ref "R23") (pin "1") (pinfunction "1_1") (pintype "passive"))
    )
    (net (code "20") (name "/OUT_0") (class "Default")
      (node (ref "J1") (pin "100") (pinfunction "100_100") (pintype "passive"))
      (node (ref "R34") (pin "1") (pinfunction "1_1") (pintype "passive"))
    )
    (net (code "21") (name "/OUT_1") (class "Default")
      (node (ref "J1") (pin "101") (pinfunction "101_101") (pintype "passive"))
      (node (ref "R33") (pin "1") (pinfunction "1_1") (pintype "passive"))
    )
    (net (code "22") (name "/OUT_2") (class "Default")
      (node (ref "J1") (pin "102") (pinfunction "102_102") (pintype "passive"))
      (node (ref "R32") (pin "1") (pinfunction "1_1") (pintype "passive"))
    )
    (net (code "23") (name "/OUT_3") (class "Default")
      (node (ref "J1") (pin "103") (pinfunction "103_103") (pintype "passive"))
      (node (ref "R31") (pin "1") (pinfunction "1_1") (pintype "passive"))
    )
    (net (code "24") (name "/OUT_4") (class "Default")
      (node (ref "J1") (pin "104") (pinfunction "104_104") (pintype "passive"))
      (node (ref "R30") (pin "1") (pinfunction "1_1") (pintype "passive"))
    )
    (net (code "25") (name "/OUT_5") (class "Default")
      (node (ref "J1") (pin "105") (pinfunction "105_105") (pintype "passive"))
      (node (ref "R29") (pin "1") (pinfunction "1_1") (pintype "passive"))
    )
    (net (code "26") (name "/OUT_6") (class "Default")
      (node (ref "J1") (pin "106") (pinfunction "106_106") (pintype "passive"))
      (node (ref "R28") (pin "1") (pinfunction "1_1") (pintype "passive"))
    )
    (net (code "27") (name "/OUT_7") (class "Default")
      (node (ref "J1") (pin "107") (pinfunction "107_107") (pintype "passive"))
      (node (ref "R27") (pin "1") (pinfunction "1_1") (pintype "passive"))
    )
    (net (code "28") (name "/POWER_GOOD") (class "Default")
      (node (ref "J1") (pin "133") (pinfunction "133_133") (pintype "passive"))
      (node (ref "R15") (pin "2") (pinfunction "2_2") (pintype "passive"))
    )
    (net (code "29") (name "/PWM_0") (class "Default")
      (node (ref "J1") (pin "59") (pinfunction "59_59") (pintype "passive"))
      (node (ref "R22") (pin "1") (pinfunction "1_1") (pintype "passive"))
    )
    (net (code "30") (name "/PWM_1") (class "Default")
      (node (ref "J1") (pin "28") (pinfunction "28_28") (pintype "passive"))
      (node (ref "R21") (pin "1") (pinfunction "1_1") (pintype "passive"))
    )
    (net (code "31") (name "/PWM_2") (class "Default")
      (node (ref "J1") (pin "30") (pinfunction "30_30") (pintype "passive"))
      (node (ref "R20") (pin "1") (pinfunction "1_1") (pintype "passive"))
    )
    (net (code "32") (name "/PWM_3") (class "Default")
      (node (ref "J1") (pin "67") (pinfunction "67_67") (pintype "passive"))
      (node (ref "R19") (pin "1") (pinfunction "1_1") (pintype "passive"))
    )
    (net (code "33") (name "/P_OUT_EN") (class "Default")
      (node (ref "J1") (pin "127") (pinfunction "127_127") (pintype "passive"))
      (node (ref "R18") (pin "2") (pinfunction "2_2") (pintype "passive"))
    )
    (net (code "34") (name "/RDY_L_1") (class "Default")
      (node (ref "J1") (pin "190") (pinfunction "190_190") (pintype "passive"))
      (node (ref "R7") (pin "2") (pinfunction "2_2") (pintype "passive"))
    )
    (net (code "35") (name "/RDY_L_2") (class "Default")
      (node (ref "J1") (pin "192") (pinfunction "192_192") (pintype "passive"))
      (node (ref "R8") (pin "2") (pinfunction "2_2") (pintype "passive"))
    )
    (net (code "36") (name "/UART1_RX") (class "Default")
      (node (ref "J1") (pin "33") (pinfunction "33_33") (pintype "passive"))
      (node (ref "R1") (pin "1") (pinfunction "1_1") (pintype "passive"))
    )
    (net (code "37") (name "/UART1_TX") (class "Default")
      (node (ref "J1") (pin "35") (pinfunction "35_35") (pintype "passive"))
      (node (ref "R2") (pin "1") (pinfunction "1_1") (pintype "passive"))
    )
    (net (code "38") (name "GND") (class "Default")
      (node (ref "C10") (pin "2") (pinfunction "2_2") (pintype "passive"))
      (node (ref "C11") (pin "2") (pinfunction "2_2") (pintype "passive"))
      (node (ref "C12") (pin "2") (pinfunction "2_2") (pintype "passive"))
      (node (ref "C13") (pin "2") (pinfunction "2_2") (pintype "passive"))
      (node (ref "C14") (pin "2") (pinfunction "2_2") (pintype "passive"))
      (node (ref "C2") (pin "2") (pinfunction "2_2") (pintype "passive"))
      (node (ref "C4") (pin "2") (pinfunction "2_2") (pintype "passive"))
      (node (ref "C5") (pin "2") (pinfunction "2_2") (pintype "passive"))
      (node (ref "C6") (pin "2") (pinfunction "2_2") (pintype "passive"))
      (node (ref "C7") (pin "2") (pinfunction "2_2") (pintype "passive"))
      (node (ref "C8") (pin "2") (pinfunction "2_2") (pintype "passive"))
      (node (ref "C9") (pin "2") (pinfunction "2_2") (pintype "passive"))
      (node (ref "J1") (pin "109") (pinfunction "109_109") (pintype "passive"))
      (node (ref "J1") (pin "11") (pinfunction "11_11") (pintype "passive"))
      (node (ref "J1") (pin "147") (pinfunction "147_147") (pintype "passive"))
      (node (ref "J1") (pin "181") (pinfunction "181_181") (pintype "passive"))
      (node (ref "J1") (pin "197") (pinfunction "197_197") (pintype "passive"))
      (node (ref "J1") (pin "199") (pinfunction "199_199") (pintype "passive"))
      (node (ref "J1") (pin "39") (pinfunction "39_39") (pintype "passive"))
      (node (ref "J1") (pin "41") (pinfunction "41_41") (pintype "passive"))
      (node (ref "J1") (pin "83") (pinfunction "83_83") (pintype "passive"))
      (node (ref "J1") (pin "9") (pinfunction "9_9") (pintype "passive"))
      (node (ref "J1") (pin "S1") (pinfunction "SHIELD_S1") (pintype "passive"))
      (node (ref "J1") (pin "S2") (pinfunction "SHIELD_S2") (pintype "passive"))
      (node (ref "J2") (pin "3") (pinfunction "3_3") (pintype "passive"))
      (node (ref "J2") (pin "4") (pinfunction "4_4") (pintype "passive"))
      (node (ref "J3") (pin "2") (pinfunction "2_2") (pintype "passive"))
      (node (ref "J3") (pin "30") (pinfunction "30_30") (pintype "passive"))
      (node (ref "J3") (pin "38") (pinfunction "38_38") (pintype "passive"))
      (node (ref "J3") (pin "48") (pinfunction "48_48") (pintype "passive"))
      (node (ref "J3") (pin "54") (pinfunction "54_54") (pintype "passive"))
      (node (ref "J3") (pin "60") (pinfunction "60_60") (pintype "passive"))
      (node (ref "MH1") (pin "1") (pinfunction "1_1") (pintype "passive"))
      (node (ref "MH2") (pin "1") (pinfunction "1_1") (pintype "passive"))
      (node (ref "MH3") (pin "1") (pinfunction "1_1") (pintype "passive"))
      (node (ref "MH4") (pin "1") (pinfunction "1_1") (pintype "passive"))
      (node (ref "TP4") (pin "1") (pinfunction "1_1") (pintype "passive"))
    )
    (net (code "39") (name "Net-(J2-Pad1)") (class "Default")
      (node (ref "J2") (pin "1") (pinfunction "1_1") (pintype "passive"))
      (node (ref "R1") (pin "2") (pinfunction "2_2") (pintype "passive"))
    )
    (net (code "40") (name "Net-(J2-Pad2)") (class "Default")
      (node (ref "J2") (pin "2") (pinfunction "2_2") (pintype "passive"))
      (node (ref "R2") (pin "2") (pinfunction "2_2") (pintype "passive"))
    )
    (net (code "41") (name "Net-(J3-Pad3)") (class "Default")
      (node (ref "J3") (pin "3") (pinfunction "3_3") (pintype "passive"))
      (node (ref "R34") (pin "2") (pinfunction "2_2") (pintype "passive"))
    )
    (net (code "42") (name "Net-(J3-Pad4)") (class "Default")
      (node (ref "J3") (pin "4") (pinfunction "4_4") (pintype "passive"))
      (node (ref "R18") (pin "1") (pinfunction "1_1") (pintype "passive"))
    )
    (net (code "43") (name "Net-(J3-Pad5)") (class "Default")
      (node (ref "J3") (pin "5") (pinfunction "5_5") (pintype "passive"))
      (node (ref "R33") (pin "2") (pinfunction "2_2") (pintype "passive"))
    )
    (net (code "44") (name "Net-(J3-Pad6)") (class "Default")
      (node (ref "J3") (pin "6") (pinfunction "6_6") (pintype "passive"))
      (node (ref "R17") (pin "1") (pinfunction "1_1") (pintype "passive"))
    )
    (net (code "45") (name "Net-(J3-Pad7)") (class "Default")
      (node (ref "J3") (pin "7") (pinfunction "7_7") (pintype "passive"))
      (node (ref "R32") (pin "2") (pinfunction "2_2") (pintype "passive"))
    )
    (net (code "46") (name "Net-(J3-Pad8)") (class "Default")
      (node (ref "J3") (pin "8") (pinfunction "8_8") (pintype "passive"))
      (node (ref "R16") (pin "1") (pinfunction "1_1") (pintype "passive"))
    )
    (net (code "47") (name "Net-(J3-Pad9)") (class "Default")
      (node (ref "J3") (pin "9") (pinfunction "9_9") (pintype "passive"))
      (node (ref "R31") (pin "2") (pinfunction "2_2") (pintype "passive"))
    )
    (net (code "48") (name "Net-(J3-Pad10)") (class "Default")
      (node (ref "J3") (pin "10") (pinfunction "10_10") (pintype "passive"))
      (node (ref "R15") (pin "1") (pinfunction "1_1") (pintype "passive"))
    )
    (net (code "49") (name "Net-(J3-Pad11)") (class "Default")
      (node (ref "J3") (pin "11") (pinfunction "11_11") (pintype "passive"))
      (node (ref "R30") (pin "2") (pinfunction "2_2") (pintype "passive"))
    )
    (net (code "50") (name "Net-(J3-Pad12)") (class "Default")
      (node (ref "J3") (pin "12") (pinfunction "12_12") (pintype "passive"))
      (node (ref "R14") (pin "1") (pinfunction "1_1") (pintype "passive"))
    )
    (net (code "51") (name "Net-(J3-Pad13)") (class "Default")
      (node (ref "J3") (pin "13") (pinfunction "13_13") (pintype "passive"))
      (node (ref "R29") (pin "2") (pinfunction "2_2") (pintype "passive"))
    )
    (net (code "52") (name "Net-(J3-Pad14)") (class "Default")
      (node (ref "J3") (pin "14") (pinfunction "14_14") (pintype "passive"))
      (node (ref "R13") (pin "1") (pinfunction "1_1") (pintype "passive"))
    )
    (net (code "53") (name "Net-(J3-Pad15)") (class "Default")
      (node (ref "J3") (pin "15") (pinfunction "15_15") (pintype "passive"))
      (node (ref "R28") (pin "2") (pinfunction "2_2") (pintype "passive"))
    )
    (net (code "54") (name "Net-(J3-Pad16)") (class "Default")
      (node (ref "J3") (pin "16") (pinfunction "16_16") (pintype "passive"))
      (node (ref "R12") (pin "1") (pinfunction "1_1") (pintype "passive"))
    )
    (net (code "55") (name "Net-(J3-Pad17)") (class "Default")
      (node (ref "J3") (pin "17") (pinfunction "17_17") (pintype "passive"))
      (node (ref "R27") (pin "2") (pinfunction "2_2") (pintype "passive"))
    )
    (net (code "56") (name "Net-(J3-Pad29)") (class "Default")
      (node (ref "J3") (pin "29") (pinfunction "29_29") (pintype "passive"))
      (node (ref "R26") (pin "2") (pinfunction "2_2") (pintype "passive"))
    )
    (net (code "57") (name "Net-(J3-Pad31)") (class "Default")
      (node (ref "J3") (pin "31") (pinfunction "31_31") (pintype "passive"))
      (node (ref "R25") (pin "2") (pinfunction "2_2") (pintype "passive"))
    )
    (net (code "58") (name "Net-(J3-Pad32)") (class "Default")
      (node (ref "J3") (pin "32") (pinfunction "32_32") (pintype "passive"))
      (node (ref "R11") (pin "1") (pinfunction "1_1") (pintype "passive"))
    )
    (net (code "59") (name "Net-(J3-Pad34)") (class "Default")
      (node (ref "J3") (pin "34") (pinfunction "34_34") (pintype "passive"))
      (node (ref "R10") (pin "1") (pinfunction "1_1") (pintype "passive"))
    )
    (net (code "60") (name "Net-(J3-Pad36)") (class "Default")
      (node (ref "J3") (pin "36") (pinfunction "36_36") (pintype "passive"))
      (node (ref "R9") (pin "1") (pinfunction "1_1") (pintype "passive"))
    )
    (net (code "61") (name "Net-(J3-Pad47)") (class "Default")
      (node (ref "J3") (pin "47") (pinfunction "47_47") (pintype "passive"))
      (node (ref "R24") (pin "2") (pinfunction "2_2") (pintype "passive"))
    )
    (net (code "62") (name "Net-(J3-Pad49)") (class "Default")
      (node (ref "J3") (pin "49") (pinfunction "49_49") (pintype "passive"))
      (node (ref "R23") (pin "2") (pinfunction "2_2") (pintype "passive"))
    )
    (net (code "63") (name "Net-(J3-Pad51)") (class "Default")
      (node (ref "J3") (pin "51") (pinfunction "51_51") (pintype "passive"))
      (node (ref "R22") (pin "2") (pinfunction "2_2") (pintype "passive"))
    )
    (net (code "64") (name "Net-(J3-Pad53)") (class "Default")
      (node (ref "J3") (pin "53") (pinfunction "53_53") (pintype "passive"))
      (node (ref "R21") (pin "2") (pinfunction "2_2") (pintype "passive"))
    )
    (net (code "65") (name "Net-(J3-Pad55)") (class "Default")
      (node (ref "J3") (pin "55") (pinfunction "55_55") (pintype "passive"))
      (node (ref "R20") (pin "2") (pinfunction "2_2") (pintype "passive"))
    )
    (net (code "66") (name "Net-(J3-Pad56)") (class "Default")
      (node (ref "J3") (pin "56") (pinfunction "56_56") (pintype "passive"))
      (node (ref "R8") (pin "1") (pinfunction "1_1") (pintype "passive"))
    )
    (net (code "67") (name "Net-(J3-Pad57)") (class "Default")
      (node (ref "J3") (pin "57") (pinfunction "57_57") (pintype "passive"))
      (node (ref "R19") (pin "2") (pinfunction "2_2") (pintype "passive"))
    )
    (net (code "68") (name "Net-(J3-Pad58)") (class "Default")
      (node (ref "J3") (pin "58") (pinfunction "58_58") (pintype "passive"))
      (node (ref "R7") (pin "1") (pinfunction "1_1") (pintype "passive"))
    )
    (net (code "69") (name "VCC3V3") (class "Default")
      (node (ref "C10") (pin "1") (pinfunction "1_1") (pintype "passive"))
      (node (ref "C11") (pin "1") (pinfunction "1_1") (pintype "passive"))
      (node (ref "C12") (pin "1") (pinfunction "1_1") (pintype "passive"))
      (node (ref "C13") (pin "1") (pinfunction "1_1") (pintype "passive"))
      (node (ref "C14") (pin "1") (pinfunction "1_1") (pintype "passive"))
      (node (ref "C2") (pin "1") (pinfunction "1_1") (pintype "passive"))
      (node (ref "C4") (pin "1") (pinfunction "1_1") (pintype "passive"))
      (node (ref "C5") (pin "1") (pinfunction "1_1") (pintype "passive"))
      (node (ref "C6") (pin "1") (pinfunction "1_1") (pintype "passive"))
      (node (ref "C7") (pin "1") (pinfunction "1_1") (pintype "passive"))
      (node (ref "C8") (pin "1") (pinfunction "1_1") (pintype "passive"))
      (node (ref "C9") (pin "1") (pinfunction "1_1") (pintype "passive"))
      (node (ref "J1") (pin "10") (pinfunction "10_10") (pintype "passive"))
      (node (ref "J1") (pin "108") (pinfunction "108_108") (pintype "passive"))
      (node (ref "J1") (pin "12") (pinfunction "12_12") (pintype "passive"))
      (node (ref "J1") (pin "148") (pinfunction "148_148") (pintype "passive"))
      (node (ref "J1") (pin "182") (pinfunction "182_182") (pintype "passive"))
      (node (ref "J1") (pin "198") (pinfunction "198_198") (pintype "passive"))
      (node (ref "J1") (pin "200") (pinfunction "200_200") (pintype "passive"))
      (node (ref "J1") (pin "42") (pinfunction "42_42") (pintype "passive"))
      (node (ref "J1") (pin "84") (pinfunction "84_84") (pintype "passive"))
      (node (ref "J3") (pin "1") (pinfunction "1_1") (pintype "passive"))
      (node (ref "J3") (pin "19") (pinfunction "19_19") (pintype "passive"))
      (node (ref "J3") (pin "27") (pinfunction "27_27") (pintype "passive"))
      (node (ref "J3") (pin "33") (pinfunction "33_33") (pintype "passive"))
      (node (ref "J3") (pin "45") (pinfunction "45_45") (pintype "passive"))
      (node (ref "J3") (pin "59") (pinfunction "59_59") (pintype "passive"))
      (node (ref "TP3") (pin "1") (pinfunction "1_1") (pintype "passive"))
    )
    (net (code "70") (name "unconnected-(J1-Pad1)") (class "Default")
      (node (ref "J1") (pin "1") (pinfunction "1_1") (pintype "passive+no_connect"))
    )
    (net (code "71") (name "unconnected-(J1-Pad2)") (class "Default")
      (node (ref "J1") (pin "2") (pinfunction "2_2") (pintype "passive+no_connect"))
    )
    (net (code "72") (name "unconnected-(J1-Pad3)") (class "Default")
      (node (ref "J1") (pin "3") (pinfunction "3_3") (pintype "passive+no_connect"))
    )
    (net (code "73") (name "unconnected-(J1-Pad4)") (class "Default")
      (node (ref "J1") (pin "4") (pinfunction "4_4") (pintype "passive+no_connect"))
    )
    (net (code "74") (name "unconnected-(J1-Pad5)") (class "Default")
      (node (ref "J1") (pin "5") (pinfunction "5_5") (pintype "passive+no_connect"))
    )
    (net (code "75") (name "unconnected-(J1-Pad6)") (class "Default")
      (node (ref "J1") (pin "6") (pinfunction "6_6") (pintype "passive+no_connect"))
    )
    (net (code "76") (name "unconnected-(J1-Pad7)") (class "Default")
      (node (ref "J1") (pin "7") (pinfunction "7_7") (pintype "passive+no_connect"))
    )
    (net (code "77") (name "unconnected-(J1-Pad8)") (class "Default")
      (node (ref "J1") (pin "8") (pinfunction "8_8") (pintype "passive+no_connect"))
    )
    (net (code "78") (name "unconnected-(J1-Pad13)") (class "Default")
      (node (ref "J1") (pin "13") (pinfunction "13_13") (pintype "passive+no_connect"))
    )
    (net (code "79") (name "unconnected-(J1-Pad14)") (class "Default")
      (node (ref "J1") (pin "14") (pinfunction "14_14") (pintype "passive+no_connect"))
    )
    (net (code "80") (name "unconnected-(J1-Pad15)") (class "Default")
      (node (ref "J1") (pin "15") (pinfunction "15_15") (pintype "passive+no_connect"))
    )
    (net (code "81") (name "unconnected-(J1-Pad16)") (class "Default")
      (node (ref "J1") (pin "16") (pinfunction "16_16") (pintype "passive+no_connect"))
    )
    (net (code "82") (name "unconnected-(J1-Pad17)") (class "Default")
      (node (ref "J1") (pin "17") (pinfunction "17_17") (pintype "passive+no_connect"))
    )
    (net (code "83") (name "unconnected-(J1-Pad18)") (class "Default")
      (node (ref "J1") (pin "18") (pinfunction "18_18") (pintype "passive+no_connect"))
    )
    (net (code "84") (name "unconnected-(J1-Pad19)") (class "Default")
      (node (ref "J1") (pin "19") (pinfunction "19_19") (pintype "passive+no_connect"))
    )
    (net (code "85") (name "unconnected-(J1-Pad20)") (class "Default")
      (node (ref "J1") (pin "20") (pinfunction "20_20") (pintype "passive+no_connect"))
    )
    (net (code "86") (name "unconnected-(J1-Pad21)") (class "Default")
      (node (ref "J1") (pin "21") (pinfunction "21_21") (pintype "passive+no_connect"))
    )
    (net (code "87") (name "unconnected-(J1-Pad22)") (class "Default")
      (node (ref "J1") (pin "22") (pinfunction "22_22") (pintype "passive+no_connect"))
    )
    (net (code "88") (name "unconnected-(J1-Pad23)") (class "Default")
      (node (ref "J1") (pin "23") (pinfunction "23_23") (pintype "passive+no_connect"))
    )
    (net (code "89") (name "unconnected-(J1-Pad24)") (class "Default")
      (node (ref "J1") (pin "24") (pinfunction "24_24") (pintype "passive+no_connect"))
    )
    (net (code "90") (name "unconnected-(J1-Pad25)") (class "Default")
      (node (ref "J1") (pin "25") (pinfunction "25_25") (pintype "passive+no_connect"))
    )
    (net (code "91") (name "unconnected-(J1-Pad26)") (class "Default")
      (node (ref "J1") (pin "26") (pinfunction "26_26") (pintype "passive+no_connect"))
    )
    (net (code "92") (name "unconnected-(J1-Pad27)") (class "Default")
      (node (ref "J1") (pin "27") (pinfunction "27_27") (pintype "passive+no_connect"))
    )
    (net (code "93") (name "unconnected-(J1-Pad29)") (class "Default")
      (node (ref "J1") (pin "29") (pinfunction "29_29") (pintype "passive+no_connect"))
    )
    (net (code "94") (name "unconnected-(J1-Pad31)") (class "Default")
      (node (ref "J1") (pin "31") (pinfunction "31_31") (pintype "passive+no_connect"))
    )
    (net (code "95") (name "unconnected-(J1-Pad37)") (class "Default")
      (node (ref "J1") (pin "37") (pinfunction "37_37") (pintype "passive+no_connect"))
    )
    (net (code "96") (name "unconnected-(J1-Pad43)") (class "Default")
      (node (ref "J1") (pin "43") (pinfunction "43_43") (pintype "passive+no_connect"))
    )
    (net (code "97") (name "unconnected-(J1-Pad44)") (class "Default")
      (node (ref "J1") (pin "44") (pinfunction "44_44") (pintype "passive+no_connect"))
    )
    (net (code "98") (name "unconnected-(J1-Pad45)") (class "Default")
      (node (ref "J1") (pin "45") (pinfunction "45_45") (pintype "passive+no_connect"))
    )
    (net (code "99") (name "unconnected-(J1-Pad46)") (class "Default")
      (node (ref "J1") (pin "46") (pinfunction "46_46") (pintype "passive+no_connect"))
    )
    (net (code "100") (name "unconnected-(J1-Pad47)") (class "Default")
      (node (ref "J1") (pin "47") (pinfunction "47_47") (pintype "passive+no_connect"))
    )
    (net (code "101") (name "unconnected-(J1-Pad48)") (class "Default")
      (node (ref "J1") (pin "48") (pinfunction "48_48") (pintype "passive+no_connect"))
    )
    (net (code "102") (name "unconnected-(J1-Pad49)") (class "Default")
      (node (ref "J1") (pin "49") (pinfunction "49_49") (pintype "passive+no_connect"))
    )
    (net (code "103") (name "unconnected-(J1-Pad50)") (class "Default")
      (node (ref "J1") (pin "50") (pinfunction "50_50") (pintype "passive+no_connect"))
    )
    (net (code "104") (name "unconnected-(J1-Pad51)") (class "Default")
      (node (ref "J1") (pin "51") (pinfunction "51_51") (pintype "passive+no_connect"))
    )
    (net (code "105") (name "unconnected-(J1-Pad52)") (class "Default")
      (node (ref "J1") (pin "52") (pinfunction "52_52") (pintype "passive+no_connect"))
    )
    (net (code "106") (name "unconnected-(J1-Pad53)") (class "Default")
      (node (ref "J1") (pin "53") (pinfunction "53_53") (pintype "passive+no_connect"))
    )
    (net (code "107") (name "unconnected-(J1-Pad54)") (class "Default")
      (node (ref "J1") (pin "54") (pinfunction "54_54") (pintype "passive+no_connect"))
    )
    (net (code "108") (name "unconnected-(J1-Pad55)") (class "Default")
      (node (ref "J1") (pin "55") (pinfunction "55_55") (pintype "passive+no_connect"))
    )
    (net (code "109") (name "unconnected-(J1-Pad56)") (class "Default")
      (node (ref "J1") (pin "56") (pinfunction "56_56") (pintype "passive+no_connect"))
    )
    (net (code "110") (name "unconnected-(J1-Pad58)") (class "Default")
      (node (ref "J1") (pin "58") (pinfunction "58_58") (pintype "passive+no_connect"))
    )
    (net (code "111") (name "unconnected-(J1-Pad60)") (class "Default")
      (node (ref "J1") (pin "60") (pinfunction "60_60") (pintype "passive+no_connect"))
    )
    (net (code "112") (name "unconnected-(J1-Pad61)") (class "Default")
      (node (ref "J1") (pin "61") (pinfunction "61_61") (pintype "passive+no_connect"))
    )
    (net (code "113") (name "unconnected-(J1-Pad62)") (class "Default")
      (node (ref "J1") (pin "62") (pinfunction "62_62") (pintype "passive+no_connect"))
    )
    (net (code "114") (name "unconnected-(J1-Pad63)") (class "Default")
      (node (ref "J1") (pin "63") (pinfunction "63_63") (pintype "passive+no_connect"))
    )
    (net (code "115") (name "unconnected-(J1-Pad64)") (class "Default")
      (node (ref "J1") (pin "64") (pinfunction "64_64") (pintype "passive+no_connect"))
    )
    (net (code "116") (name "unconnected-(J1-Pad66)") (class "Default")
      (node (ref "J1") (pin "66") (pinfunction "66_66") (pintype "passive+no_connect"))
    )
    (net (code "117") (name "unconnected-(J1-Pad68)") (class "Default")
      (node (ref "J1") (pin "68") (pinfunction "68_68") (pintype "passive+no_connect"))
    )
    (net (code "118") (name "unconnected-(J1-Pad69)") (class "Default")
      (node (ref "J1") (pin "69") (pinfunction "69_69") (pintype "passive+no_connect"))
    )
    (net (code "119") (name "unconnected-(J1-Pad70)") (class "Default")
      (node (ref "J1") (pin "70") (pinfunction "70_70") (pintype "passive+no_connect"))
    )
    (net (code "120") (name "unconnected-(J1-Pad71)") (class "Default")
      (node (ref "J1") (pin "71") (pinfunction "71_71") (pintype "passive+no_connect"))
    )
    (net (code "121") (name "unconnected-(J1-Pad72)") (class "Default")
      (node (ref "J1") (pin "72") (pinfunction "72_72") (pintype "passive+no_connect"))
    )
    (net (code "122") (name "unconnected-(J1-Pad73)") (class "Default")
      (node (ref "J1") (pin "73") (pinfunction "73_73") (pintype "passive+no_connect"))
    )
    (net (code "123") (name "unconnected-(J1-Pad74)") (class "Default")
      (node (ref "J1") (pin "74") (pinfunction "74_74") (pintype "passive+no_connect"))
    )
    (net (code "124") (name "unconnected-(J1-Pad75)") (class "Default")
      (node (ref "J1") (pin "75") (pinfunction "75_75") (pintype "passive+no_connect"))
    )
    (net (code "125") (name "unconnected-(J1-Pad76)") (class "Default")
      (node (ref "J1") (pin "76") (pinfunction "76_76") (pintype "passive+no_connect"))
    )
    (net (code "126") (name "unconnected-(J1-Pad77)") (class "Default")
      (node (ref "J1") (pin "77") (pinfunction "77_77") (pintype "passive+no_connect"))
    )
    (net (code "127") (name "unconnected-(J1-Pad78)") (class "Default")
      (node (ref "J1") (pin "78") (pinfunction "78_78") (pintype "passive+no_connect"))
    )
    (net (code "128") (name "unconnected-(J1-Pad79)") (class "Default")
      (node (ref "J1") (pin "79") (pinfunction "79_79") (pintype "passive+no_connect"))
    )
    (net (code "129") (name "unconnected-(J1-Pad80)") (class "Default")
      (node (ref "J1") (pin "80") (pinfunction "80_80") (pintype "passive+no_connect"))
    )
    (net (code "130") (name "unconnected-(J1-Pad81)") (class "Default")
      (node (ref "J1") (pin "81") (pinfunction "81_81") (pintype "passive+no_connect"))
    )
    (net (code "131") (name "unconnected-(J1-Pad82)") (class "Default")
      (node (ref "J1") (pin "82") (pinfunction "82_82") (pintype "passive+no_connect"))
    )
    (net (code "132") (name "unconnected-(J1-Pad85)") (class "Default")
      (node (ref "J1") (pin "85") (pinfunction "85_85") (pintype "passive+no_connect"))
    )
    (net (code "133") (name "unconnected-(J1-Pad86)") (class "Default")
      (node (ref "J1") (pin "86") (pinfunction "86_86") (pintype "passive+no_connect"))
    )
    (net (code "134") (name "unconnected-(J1-Pad87)") (class "Default")
      (node (ref "J1") (pin "87") (pinfunction "87_87") (pintype "passive+no_connect"))
    )
    (net (code "135") (name "unconnected-(J1-Pad88)") (class "Default")
      (node (ref "J1") (pin "88") (pinfunction "88_88") (pintype "passive+no_connect"))
    )
    (net (code "136") (name "unconnected-(J1-Pad89)") (class "Default")
      (node (ref "J1") (pin "89") (pinfunction "89_89") (pintype "passive+no_connect"))
    )
    (net (code "137") (name "unconnected-(J1-Pad90)") (class "Default")
      (node (ref "J1") (pin "90") (pinfunction "90_90") (pintype "passive+no_connect"))
    )
    (net (code "138") (name "unconnected-(J1-Pad91)") (class "Default")
      (node (ref "J1") (pin "91") (pinfunction "91_91") (pintype "passive+no_connect"))
    )
    (net (code "139") (name "unconnected-(J1-Pad92)") (class "Default")
      (node (ref "J1") (pin "92") (pinfunction "92_92") (pintype "passive+no_connect"))
    )
    (net (code "140") (name "unconnected-(J1-Pad93)") (class "Default")
      (node (ref "J1") (pin "93") (pinfunction "93_93") (pintype "passive+no_connect"))
    )
    (net (code "141") (name "unconnected-(J1-Pad94)") (class "Default")
      (node (ref "J1") (pin "94") (pinfunction "94_94") (pintype "passive+no_connect"))
    )
    (net (code "142") (name "unconnected-(J1-Pad95)") (class "Default")
      (node (ref "J1") (pin "95") (pinfunction "95_95") (pintype "passive+no_connect"))
    )
    (net (code "143") (name "unconnected-(J1-Pad96)") (class "Default")
      (node (ref "J1") (pin "96") (pinfunction "96_96") (pintype "passive+no_connect"))
    )
    (net (code "144") (name "unconnected-(J1-Pad97)") (class "Default")
      (node (ref "J1") (pin "97") (pinfunction "97_97") (pintype "passive+no_connect"))
    )
    (net (code "145") (name "unconnected-(J1-Pad98)") (class "Default")
      (node (ref "J1") (pin "98") (pinfunction "98_98") (pintype "passive+no_connect"))
    )
    (net (code "146") (name "unconnected-(J1-Pad99)") (class "Default")
      (node (ref "J1") (pin "99") (pinfunction "99_99") (pintype "passive+no_connect"))
    )
    (net (code "147") (name "unconnected-(J1-Pad110)") (class "Default")
      (node (ref "J1") (pin "110") (pinfunction "110_110") (pintype "passive+no_connect"))
    )
    (net (code "148") (name "unconnected-(J1-Pad111)") (class "Default")
      (node (ref "J1") (pin "111") (pinfunction "111_111") (pintype "passive+no_connect"))
    )
    (net (code "149") (name "unconnected-(J1-Pad112)") (class "Default")
      (node (ref "J1") (pin "112") (pinfunction "112_112") (pintype "passive+no_connect"))
    )
    (net (code "150") (name "unconnected-(J1-Pad113)") (class "Default")
      (node (ref "J1") (pin "113") (pinfunction "113_113") (pintype "passive+no_connect"))
    )
    (net (code "151") (name "unconnected-(J1-Pad114)") (class "Default")
      (node (ref "J1") (pin "114") (pinfunction "114_114") (pintype "passive+no_connect"))
    )
    (net (code "152") (name "unconnected-(J1-Pad115)") (class "Default")
      (node (ref "J1") (pin "115") (pinfunction "115_115") (pintype "passive+no_connect"))
    )
    (net (code "153") (name "unconnected-(J1-Pad116)") (class "Default")
      (node (ref "J1") (pin "116") (pinfunction "116_116") (pintype "passive+no_connect"))
    )
    (net (code "154") (name "unconnected-(J1-Pad117)") (class "Default")
      (node (ref "J1") (pin "117") (pinfunction "117_117") (pintype "passive+no_connect"))
    )
    (net (code "155") (name "unconnected-(J1-Pad118)") (class "Default")
      (node (ref "J1") (pin "118") (pinfunction "118_118") (pintype "passive+no_connect"))
    )
    (net (code "156") (name "unconnected-(J1-Pad119)") (class "Default")
      (node (ref "J1") (pin "119") (pinfunction "119_119") (pintype "passive+no_connect"))
    )
    (net (code "157") (name "unconnected-(J1-Pad120)") (class "Default")
      (node (ref "J1") (pin "120") (pinfunction "120_120") (pintype "passive+no_connect"))
    )
    (net (code "158") (name "unconnected-(J1-Pad121)") (class "Default")
      (node (ref "J1") (pin "121") (pinfunction "121_121") (pintype "passive+no_connect"))
    )
    (net (code "159") (name "unconnected-(J1-Pad122)") (class "Default")
      (node (ref "J1") (pin "122") (pinfunction "122_122") (pintype "passive+no_connect"))
    )
    (net (code "160") (name "unconnected-(J1-Pad123)") (class "Default")
      (node (ref "J1") (pin "123") (pinfunction "123_123") (pintype "passive+no_connect"))
    )
    (net (code "161") (name "unconnected-(J1-Pad124)") (class "Default")
      (node (ref "J1") (pin "124") (pinfunction "124_124") (pintype "passive+no_connect"))
    )
    (net (code "162") (name "unconnected-(J1-Pad125)") (class "Default")
      (node (ref "J1") (pin "125") (pinfunction "125_125") (pintype "passive+no_connect"))
    )
    (net (code "163") (name "unconnected-(J1-Pad126)") (class "Default")
      (node (ref "J1") (pin "126") (pinfunction "126_126") (pintype "passive+no_connect"))
    )
    (net (code "164") (name "unconnected-(J1-Pad128)") (class "Default")
      (node (ref "J1") (pin "128") (pinfunction "128_128") (pintype "passive+no_connect"))
    )
    (net (code "165") (name "unconnected-(J1-Pad130)") (class "Default")
      (node (ref "J1") (pin "130") (pinfunction "130_130") (pintype "passive+no_connect"))
    )
    (net (code "166") (name "unconnected-(J1-Pad132)") (class "Default")
      (node (ref "J1") (pin "132") (pinfunction "132_132") (pintype "passive+no_connect"))
    )
    (net (code "167") (name "unconnected-(J1-Pad134)") (class "Default")
      (node (ref "J1") (pin "134") (pinfunction "134_134") (pintype "passive+no_connect"))
    )
    (net (code "168") (name "unconnected-(J1-Pad136)") (class "Default")
      (node (ref "J1") (pin "136") (pinfunction "136_136") (pintype "passive+no_connect"))
    )
    (net (code "169") (name "unconnected-(J1-Pad139)") (class "Default")
      (node (ref "J1") (pin "139") (pinfunction "139_139") (pintype "passive+no_connect"))
    )
    (net (code "170") (name "unconnected-(J1-Pad140)") (class "Default")
      (node (ref "J1") (pin "140") (pinfunction "140_140") (pintype "passive+no_connect"))
    )
    (net (code "171") (name "unconnected-(J1-Pad141)") (class "Default")
      (node (ref "J1") (pin "141") (pinfunction "141_141") (pintype "passive+no_connect"))
    )
    (net (code "172") (name "unconnected-(J1-Pad142)") (class "Default")
      (node (ref "J1") (pin "142") (pinfunction "142_142") (pintype "passive+no_connect"))
    )
    (net (code "173") (name "unconnected-(J1-Pad143)") (class "Default")
      (node (ref "J1") (pin "143") (pinfunction "143_143") (pintype "passive+no_connect"))
    )
    (net (code "174") (name "unconnected-(J1-Pad144)") (class "Default")
      (node (ref "J1") (pin "144") (pinfunction "144_144") (pintype "passive+no_connect"))
    )
    (net (code "175") (name "unconnected-(J1-Pad145)") (class "Default")
      (node (ref "J1") (pin "145") (pinfunction "145_145") (pintype "passive+no_connect"))
    )
    (net (code "176") (name "unconnected-(J1-Pad146)") (class "Default")
      (node (ref "J1") (pin "146") (pinfunction "146_146") (pintype "passive+no_connect"))
    )
    (net (code "177") (name "unconnected-(J1-Pad149)") (class "Default")
      (node (ref "J1") (pin "149") (pinfunction "149_149") (pintype "passive+no_connect"))
    )
    (net (code "178") (name "unconnected-(J1-Pad150)") (class "Default")
      (node (ref "J1") (pin "150") (pinfunction "150_150") (pintype "passive+no_connect"))
    )
    (net (code "179") (name "unconnected-(J1-Pad151)") (class "Default")
      (node (ref "J1") (pin "151") (pinfunction "151_151") (pintype "passive+no_connect"))
    )
    (net (code "180") (name "unconnected-(J1-Pad152)") (class "Default")
      (node (ref "J1") (pin "152") (pinfunction "152_152") (pintype "passive+no_connect"))
    )
    (net (code "181") (name "unconnected-(J1-Pad153)") (class "Default")
      (node (ref "J1") (pin "153") (pinfunction "153_153") (pintype "passive+no_connect"))
    )
    (net (code "182") (name "unconnected-(J1-Pad154)") (class "Default")
      (node (ref "J1") (pin "154") (pinfunction "154_154") (pintype "passive+no_connect"))
    )
    (net (code "183") (name "unconnected-(J1-Pad155)") (class "Default")
      (node (ref "J1") (pin "155") (pinfunction "155_155") (pintype "passive+no_connect"))
    )
    (net (code "184") (name "unconnected-(J1-Pad156)") (class "Default")
      (node (ref "J1") (pin "156") (pinfunction "156_156") (pintype "passive+no_connect"))
    )
    (net (code "185") (name "unconnected-(J1-Pad157)") (class "Default")
      (node (ref "J1") (pin "157") (pinfunction "157_157") (pintype "passive+no_connect"))
    )
    (net (code "186") (name "unconnected-(J1-Pad158)") (class "Default")
      (node (ref "J1") (pin "158") (pinfunction "158_158") (pintype "passive+no_connect"))
    )
    (net (code "187") (name "unconnected-(J1-Pad159)") (class "Default")
      (node (ref "J1") (pin "159") (pinfunction "159_159") (pintype "passive+no_connect"))
    )
    (net (code "188") (name "unconnected-(J1-Pad160)") (class "Default")
      (node (ref "J1") (pin "160") (pinfunction "160_160") (pintype "passive+no_connect"))
    )
    (net (code "189") (name "unconnected-(J1-Pad161)") (class "Default")
      (node (ref "J1") (pin "161") (pinfunction "161_161") (pintype "passive+no_connect"))
    )
    (net (code "190") (name "unconnected-(J1-Pad162)") (class "Default")
      (node (ref "J1") (pin "162") (pinfunction "162_162") (pintype "passive+no_connect"))
    )
    (net (code "191") (name "unconnected-(J1-Pad163)") (class "Default")
      (node (ref "J1") (pin "163") (pinfunction "163_163") (pintype "passive+no_connect"))
    )
    (net (code "192") (name "unconnected-(J1-Pad164)") (class "Default")
      (node (ref "J1") (pin "164") (pinfunction "164_164") (pintype "passive+no_connect"))
    )
    (net (code "193") (name "unconnected-(J1-Pad165)") (class "Default")
      (node (ref "J1") (pin "165") (pinfunction "165_165") (pintype "passive+no_connect"))
    )
    (net (code "194") (name "unconnected-(J1-Pad166)") (class "Default")
      (node (ref "J1") (pin "166") (pinfunction "166_166") (pintype "passive+no_connect"))
    )
    (net (code "195") (name "unconnected-(J1-Pad167)") (class "Default")
      (node (ref "J1") (pin "167") (pinfunction "167_167") (pintype "passive+no_connect"))
    )
    (net (code "196") (name "unconnected-(J1-Pad168)") (class "Default")
      (node (ref "J1") (pin "168") (pinfunction "168_168") (pintype "passive+no_connect"))
    )
    (net (code "197") (name "unconnected-(J1-Pad169)") (class "Default")
      (node (ref "J1") (pin "169") (pinfunction "169_169") (pintype "passive+no_connect"))
    )
    (net (code "198") (name "unconnected-(J1-Pad170)") (class "Default")
      (node (ref "J1") (pin "170") (pinfunction "170_170") (pintype "passive+no_connect"))
    )
    (net (code "199") (name "unconnected-(J1-Pad171)") (class "Default")
      (node (ref "J1") (pin "171") (pinfunction "171_171") (pintype "passive+no_connect"))
    )
    (net (code "200") (name "unconnected-(J1-Pad172)") (class "Default")
      (node (ref "J1") (pin "172") (pinfunction "172_172") (pintype "passive+no_connect"))
    )
    (net (code "201") (name "unconnected-(J1-Pad173)") (class "Default")
      (node (ref "J1") (pin "173") (pinfunction "173_173") (pintype "passive+no_connect"))
    )
    (net (code "202") (name "unconnected-(J1-Pad174)") (class "Default")
      (node (ref "J1") (pin "174") (pinfunction "174_174") (pintype "passive+no_connect"))
    )
    (net (code "203") (name "unconnected-(J1-Pad175)") (class "Default")
      (node (ref "J1") (pin "175") (pinfunction "175_175") (pintype "passive+no_connect"))
    )
    (net (code "204") (name "unconnected-(J1-Pad176)") (class "Default")
      (node (ref "J1") (pin "176") (pinfunction "176_176") (pintype "passive+no_connect"))
    )
    (net (code "205") (name "unconnected-(J1-Pad177)") (class "Default")
      (node (ref "J1") (pin "177") (pinfunction "177_177") (pintype "passive+no_connect"))
    )
    (net (code "206") (name "unconnected-(J1-Pad179)") (class "Default")
      (node (ref "J1") (pin "179") (pinfunction "179_179") (pintype "passive+no_connect"))
    )
    (net (code "207") (name "unconnected-(J1-Pad180)") (class "Default")
      (node (ref "J1") (pin "180") (pinfunction "180_180") (pintype "passive+no_connect"))
    )
    (net (code "208") (name "unconnected-(J1-Pad183)") (class "Default")
      (node (ref "J1") (pin "183") (pinfunction "183_183") (pintype "passive+no_connect"))
    )
    (net (code "209") (name "unconnected-(J1-Pad184)") (class "Default")
      (node (ref "J1") (pin "184") (pinfunction "184_184") (pintype "passive+no_connect"))
    )
    (net (code "210") (name "unconnected-(J1-Pad185)") (class "Default")
      (node (ref "J1") (pin "185") (pinfunction "185_185") (pintype "passive+no_connect"))
    )
    (net (code "211") (name "unconnected-(J1-Pad187)") (class "Default")
      (node (ref "J1") (pin "187") (pinfunction "187_187") (pintype "passive+no_connect"))
    )
    (net (code "212") (name "unconnected-(J1-Pad189)") (class "Default")
      (node (ref "J1") (pin "189") (pinfunction "189_189") (pintype "passive+no_connect"))
    )
    (net (code "213") (name "unconnected-(J1-Pad191)") (class "Default")
      (node (ref "J1") (pin "191") (pinfunction "191_191") (pintype "passive+no_connect"))
    )
    (net (code "214") (name "unconnected-(J1-Pad193)") (class "Default")
      (node (ref "J1") (pin "193") (pinfunction "193_193") (pintype "passive+no_connect"))
    )
    (net (code "215") (name "unconnected-(J1-Pad195)") (class "Default")
      (node (ref "J1") (pin "195") (pinfunction "195_195") (pintype "passive+no_connect"))
    )
    (net (code "216") (name "unconnected-(J3-Pad18)") (class "Default")
      (node (ref "J3") (pin "18") (pinfunction "18_18") (pintype "passive+no_connect"))
    )
    (net (code "217") (name "unconnected-(J3-Pad20)") (class "Default")
      (node (ref "J3") (pin "20") (pinfunction "20_20") (pintype "passive+no_connect"))
    )
    (net (code "218") (name "unconnected-(J3-Pad21)") (class "Default")
      (node (ref "J3") (pin "21") (pinfunction "21_21") (pintype "passive+no_connect"))
    )
    (net (code "219") (name "unconnected-(J3-Pad22)") (class "Default")
      (node (ref "J3") (pin "22") (pinfunction "22_22") (pintype "passive+no_connect"))
    )
    (net (code "220") (name "unconnected-(J3-Pad23)") (class "Default")
      (node (ref "J3") (pin "23") (pinfunction "23_23") (pintype "passive+no_connect"))
    )
    (net (code "221") (name "unconnected-(J3-Pad24)") (class "Default")
      (node (ref "J3") (pin "24") (pinfunction "24_24") (pintype "passive+no_connect"))
    )
    (net (code "222") (name "unconnected-(J3-Pad25)") (class "Default")
      (node (ref "J3") (pin "25") (pinfunction "25_25") (pintype "passive+no_connect"))
    )
    (net (code "223") (name "unconnected-(J3-Pad26)") (class "Default")
      (node (ref "J3") (pin "26") (pinfunction "26_26") (pintype "passive+no_connect"))
    )
    (net (code "224") (name "unconnected-(J3-Pad28)") (class "Default")
      (node (ref "J3") (pin "28") (pinfunction "28_28") (pintype "passive+no_connect"))
    )
    (net (code "225") (name "unconnected-(J3-Pad35)") (class "Default")
      (node (ref "J3") (pin "35") (pinfunction "35_35") (pintype "passive+no_connect"))
    )
    (net (code "226") (name "unconnected-(J3-Pad37)") (class "Default")
      (node (ref "J3") (pin "37") (pinfunction "37_37") (pintype "passive+no_connect"))
    )
    (net (code "227") (name "unconnected-(J3-Pad39)") (class "Default")
      (node (ref "J3") (pin "39") (pinfunction "39_39") (pintype "passive+no_connect"))
    )
    (net (code "228") (name "unconnected-(J3-Pad40)") (class "Default")
      (node (ref "J3") (pin "40") (pinfunction "40_40") (pintype "passive+no_connect"))
    )
    (net (code "229") (name "unconnected-(J3-Pad41)") (class "Default")
      (node (ref "J3") (pin "41") (pinfunction "41_41") (pintype "passive+no_connect"))
    )
    (net (code "230") (name "unconnected-(J3-Pad42)") (class "Default")
      (node (ref "J3") (pin "42") (pinfunction "42_42") (pintype "passive+no_connect"))
    )
    (net (code "231") (name "unconnected-(J3-Pad44)") (class "Default")
      (node (ref "J3") (pin "44") (pinfunction "44_44") (pintype "passive+no_connect"))
    )
    (net (code "232") (name "unconnected-(J3-Pad46)") (class "Default")
      (node (ref "J3") (pin "46") (pinfunction "46_46") (pintype "passive+no_connect"))
    )
    (net (code "233") (name "unconnected-(S7-Pad1)") (class "Default")
      (node (ref "S7") (pin "1") (pinfunction "1_1") (pintype "passive+no_connect"))
    )
    (net (code "234") (name "unconnected-(S8-Pad1)") (class "Default")
      (node (ref "S8") (pin "1") (pinfunction "1_1") (pintype "passive+no_connect"))
    )
  )
)
